# CodeWithJawad-eee_MPU6050__MPU6050.net
KiCad netlist of a schematic drawn in Altium Designer
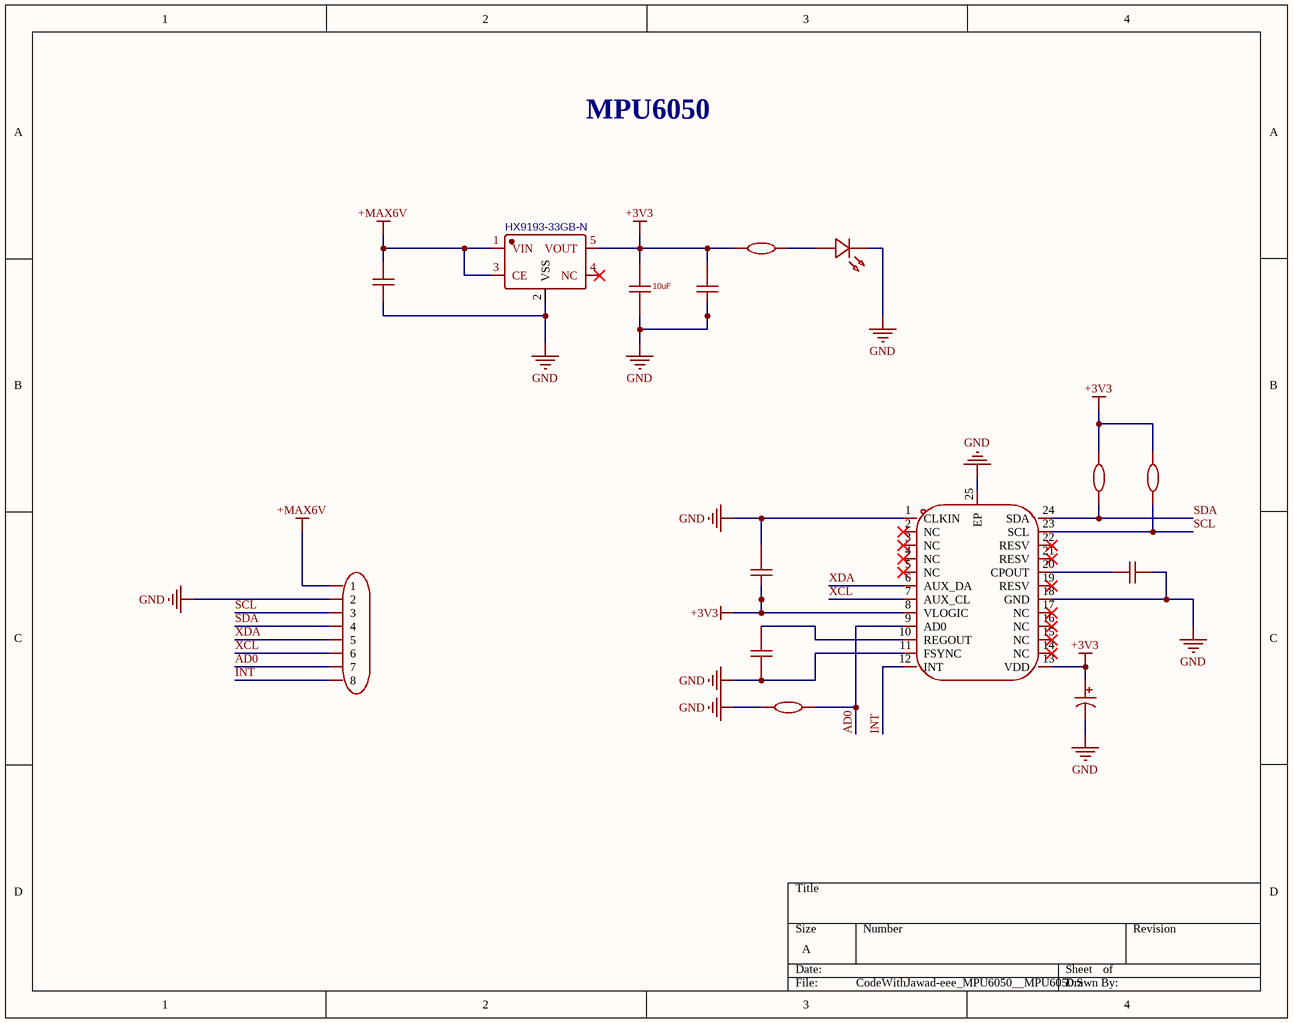
[diagram p0: CodeWithJawad-eee_MPU6050__MPU6050.SchDoc]

(export (version "E")
  (design (tool "Eeschema 10.0.6"))
  (components
    (comp (ref "C1")
      (value "100nF")
      (footprint "C0603")
      (fields
        (field (name "MANUFACTURER") "YAGEO(国巨)")
        (field (name "MANUFACTURER PART") "CC0603KRX7R9BB104")
        (field (name "TOLERANCE") "±10%")
      )
      (libsource (lib "SCH library") (part "CC0603KRX7R9BB104"))
    )
    (comp (ref "C2")
      (value "10uF")
      (footprint "C0603")
      (fields
        (field (name "MANUFACTURER") "SAMSUNG(三星)")
        (field (name "MANUFACTURER PART") "CL10A106KP8NNNC")
        (field (name "TOLERANCE") "±10%")
      )
      (libsource (lib "SCH library") (part "CL10A106KP8NNNC"))
    )
    (comp (ref "C3")
      (value "4.7uF")
      (footprint "C0603")
      (fields
        (field (name "MANUFACTURER") "SAMSUNG(三星)")
        (field (name "MANUFACTURER PART") "CL10A475KA8NQNC")
        (field (name "TOLERANCE") "±10%")
      )
      (libsource (lib "SCH library") (part "CL10A475KA8NQNC"))
    )
    (comp (ref "C4")
      (value "2.2nF")
      (footprint "C0603")
      (fields
        (field (name "MANUFACTURER") "YAGEO(国巨)")
        (field (name "MANUFACTURER PART") "CC0603KRX7R9BB222")
        (field (name "TOLERANCE") "±10%")
      )
      (libsource (lib "SCH library") (part "CC0603KRX7R9BB222"))
    )
    (comp (ref "C5")
      (value "100nF")
      (footprint "CAP-TH_BD5.0-P2.00-D0.8-FD")
      (fields
        (field (name "MANUFACTURER") "CX(承兴)")
        (field (name "MANUFACTURER PART") "KM104M050D11RR0VH2FP0")
        (field (name "TOLERANCE") "±20%")
      )
      (libsource (lib "SCH library") (part "KM104M050D11RR0VH2FP0"))
    )
    (comp (ref "C6")
      (value "100nF")
      (footprint "C0603")
      (fields
        (field (name "MANUFACTURER") "YAGEO(国巨)")
        (field (name "MANUFACTURER PART") "CC0603KRX7R9BB104")
        (field (name "TOLERANCE") "±10%")
      )
      (libsource (lib "SCH library") (part "CC0603KRX7R9BB104"))
    )
    (comp (ref "C7")
      (value "100nF")
      (footprint "C0603")
      (fields
        (field (name "MANUFACTURER") "YAGEO(国巨)")
        (field (name "MANUFACTURER PART") "CC0603KRX7R9BB104")
        (field (name "TOLERANCE") "±10%")
      )
      (libsource (lib "SCH library") (part "CC0603KRX7R9BB104"))
    )
    (comp (ref "LED1")
      (value "XL-1608SURC-06")
      (footprint "LED0603-RD_RED")
      (fields (field (name "MANUFACTURER") "XINGLIGHT(成兴光)"))
      (libsource (lib "SCH library") (part "XL-1608SURC-06"))
    )
    (comp (ref "P1")
      (value "2.54-1*8P母环保")
      (footprint "HDR-TH_8P-P2.54-V-F-1")
      (fields (field (name "MANUFACTURER") "BOOMELE(博穆精密)"))
      (libsource (lib "SCH library") (part "2.54-1*8P母环保"))
    )
    (comp (ref "R1")
      (value "2kΩ")
      (footprint "R0603")
      (fields
        (field (name "MANUFACTURER") "YAGEO(国巨)")
        (field (name "MANUFACTURER PART") "RC0603FR-072KL")
        (field (name "TOLERANCE") "±1%")
      )
      (libsource (lib "SCH library") (part "RC0603FR-072KL"))
    )
    (comp (ref "R2")
      (value "4.7kΩ")
      (footprint "R0603")
      (fields
        (field (name "MANUFACTURER") "YAGEO(国巨)")
        (field (name "MANUFACTURER PART") "RC0603FR-074K7L")
        (field (name "TOLERANCE") "±1%")
      )
      (libsource (lib "SCH library") (part "RC0603FR-074K7L"))
    )
    (comp (ref "R3")
      (value "4.7kΩ")
      (footprint "R0603")
      (fields
        (field (name "MANUFACTURER") "YAGEO(国巨)")
        (field (name "MANUFACTURER PART") "RC0603FR-074K7L")
        (field (name "TOLERANCE") "±1%")
      )
      (libsource (lib "SCH library") (part "RC0603FR-074K7L"))
    )
    (comp (ref "R4")
      (value "4.7kΩ")
      (footprint "R0603")
      (fields
        (field (name "MANUFACTURER") "YAGEO(国巨)")
        (field (name "MANUFACTURER PART") "RC0603FR-074K7L")
        (field (name "TOLERANCE") "±1%")
      )
      (libsource (lib "SCH library") (part "RC0603FR-074K7L"))
    )
    (comp (ref "U1")
      (value "HX9193-33GB-N")
      (footprint "SOT-23-5_L2.9-W1.6-P0.95-LS2.8-BL")
      (fields (field (name "MANUFACTURER") "HX(恒佳兴)") (field (name "CONTRIBUTOR") "lcsc"))
      (libsource (lib "SCH library") (part "HX9193-33GB-N"))
    )
    (comp (ref "U3")
      (value "MPU-6050")
      (footprint "QFN-24_L4.0-W4.0-P0.50-BL-EP2.7")
      (fields (field (name "MANUFACTURER") "TDK InvenSense(应美盛)"))
      (libsource (lib "SCH library") (part "MPU-6050"))
    )
  )
  (nets
    (net (code "1") (name "+3V3") (class "Default")
      (node (ref "C1") (pin "2") (pinfunction "2_2") (pintype "passive"))
      (node (ref "C2") (pin "2") (pinfunction "2_2") (pintype "passive"))
      (node (ref "C5") (pin "1") (pinfunction "1_1") (pintype "passive"))
      (node (ref "C6") (pin "1") (pinfunction "1_1") (pintype "passive"))
      (node (ref "R1") (pin "1") (pinfunction "1_1") (pintype "passive"))
      (node (ref "R2") (pin "2") (pinfunction "2_2") (pintype "passive"))
      (node (ref "R3") (pin "2") (pinfunction "2_2") (pintype "passive"))
      (node (ref "U1") (pin "5") (pinfunction "VOUT_5") (pintype "passive"))
      (node (ref "U3") (pin "13") (pinfunction "VDD_13") (pintype "passive"))
      (node (ref "U3") (pin "8") (pinfunction "VLOGIC_8") (pintype "passive"))
    )
    (net (code "2") (name "+MAX6V") (class "Default")
      (node (ref "C3") (pin "2") (pinfunction "2_2") (pintype "passive"))
      (node (ref "P1") (pin "1") (pinfunction "1_1") (pintype "passive"))
      (node (ref "U1") (pin "1") (pinfunction "VIN_1") (pintype "passive"))
      (node (ref "U1") (pin "3") (pinfunction "CE_3") (pintype "passive"))
    )
    (net (code "3") (name "/AD0") (class "Default")
      (node (ref "P1") (pin "7") (pinfunction "7_7") (pintype "passive"))
      (node (ref "R4") (pin "1") (pinfunction "1_1") (pintype "passive"))
      (node (ref "U3") (pin "9") (pinfunction "AD0_9") (pintype "passive"))
    )
    (net (code "4") (name "/INT") (class "Default")
      (node (ref "P1") (pin "8") (pinfunction "8_8") (pintype "passive"))
      (node (ref "U3") (pin "12") (pinfunction "INT_12") (pintype "passive"))
    )
    (net (code "5") (name "/SCL") (class "Default")
      (node (ref "P1") (pin "3") (pinfunction "3_3") (pintype "passive"))
      (node (ref "R3") (pin "1") (pinfunction "1_1") (pintype "passive"))
      (node (ref "U3") (pin "23") (pinfunction "SCL_23") (pintype "passive"))
    )
    (net (code "6") (name "/SDA") (class "Default")
      (node (ref "P1") (pin "4") (pinfunction "4_4") (pintype "passive"))
      (node (ref "R2") (pin "1") (pinfunction "1_1") (pintype "passive"))
      (node (ref "U3") (pin "24") (pinfunction "SDA_24") (pintype "passive"))
    )
    (net (code "7") (name "/XCL") (class "Default")
      (node (ref "P1") (pin "6") (pinfunction "6_6") (pintype "passive"))
      (node (ref "U3") (pin "7") (pinfunction "AUX_CL_7") (pintype "passive"))
    )
    (net (code "8") (name "/XDA") (class "Default")
      (node (ref "P1") (pin "5") (pinfunction "5_5") (pintype "passive"))
      (node (ref "U3") (pin "6") (pinfunction "AUX_DA_6") (pintype "passive"))
    )
    (net (code "9") (name "GND") (class "Default")
      (node (ref "C1") (pin "1") (pinfunction "1_1") (pintype "passive"))
      (node (ref "C2") (pin "1") (pinfunction "1_1") (pintype "passive"))
      (node (ref "C3") (pin "1") (pinfunction "1_1") (pintype "passive"))
      (node (ref "C4") (pin "2") (pinfunction "2_2") (pintype "passive"))
      (node (ref "C5") (pin "2") (pinfunction "2_2") (pintype "passive"))
      (node (ref "C6") (pin "2") (pinfunction "2_2") (pintype "passive"))
      (node (ref "C7") (pin "1") (pinfunction "1_1") (pintype "passive"))
      (node (ref "LED1") (pin "1") (pinfunction "K_1") (pintype "passive"))
      (node (ref "P1") (pin "2") (pinfunction "2_2") (pintype "passive"))
      (node (ref "R4") (pin "2") (pinfunction "2_2") (pintype "passive"))
      (node (ref "U1") (pin "2") (pinfunction "VSS_2") (pintype "passive"))
      (node (ref "U3") (pin "1") (pinfunction "CLKIN_1") (pintype "passive"))
      (node (ref "U3") (pin "11") (pinfunction "FSYNC_11") (pintype "passive"))
      (node (ref "U3") (pin "18") (pinfunction "GND_18") (pintype "passive"))
      (node (ref "U3") (pin "25") (pinfunction "EP_25") (pintype "passive"))
    )
    (net (code "10") (name "Net-(LED1-A)") (class "Default")
      (node (ref "LED1") (pin "2") (pinfunction "A_2") (pintype "passive"))
      (node (ref "R1") (pin "2") (pinfunction "2_2") (pintype "passive"))
    )
    (net (code "11") (name "Net-(U3-CPOUT)") (class "Default")
      (node (ref "C4") (pin "1") (pinfunction "1_1") (pintype "passive"))
      (node (ref "U3") (pin "20") (pinfunction "CPOUT_20") (pintype "passive"))
    )
    (net (code "12") (name "Net-(U3-REGOUT)") (class "Default")
      (node (ref "C7") (pin "2") (pinfunction "2_2") (pintype "passive"))
      (node (ref "U3") (pin "10") (pinfunction "REGOUT_10") (pintype "passive"))
    )
    (net (code "13") (name "unconnected-(U1-NC-Pad4)") (class "Default")
      (node (ref "U1") (pin "4") (pinfunction "NC_4") (pintype "passive+no_connect"))
    )
    (net (code "14") (name "unconnected-(U3-NC-Pad2)") (class "Default")
      (node (ref "U3") (pin "2") (pinfunction "NC_2") (pintype "passive+no_connect"))
    )
    (net (code "15") (name "unconnected-(U3-NC-Pad3)") (class "Default")
      (node (ref "U3") (pin "3") (pinfunction "NC_3") (pintype "passive+no_connect"))
    )
    (net (code "16") (name "unconnected-(U3-NC-Pad4)") (class "Default")
      (node (ref "U3") (pin "4") (pinfunction "NC_4") (pintype "passive+no_connect"))
    )
    (net (code "17") (name "unconnected-(U3-NC-Pad5)") (class "Default")
      (node (ref "U3") (pin "5") (pinfunction "NC_5") (pintype "passive+no_connect"))
    )
    (net (code "18") (name "unconnected-(U3-NC-Pad14)") (class "Default")
      (node (ref "U3") (pin "14") (pinfunction "NC_14") (pintype "passive+no_connect"))
    )
    (net (code "19") (name "unconnected-(U3-NC-Pad15)") (class "Default")
      (node (ref "U3") (pin "15") (pinfunction "NC_15") (pintype "passive+no_connect"))
    )
    (net (code "20") (name "unconnected-(U3-NC-Pad16)") (class "Default")
      (node (ref "U3") (pin "16") (pinfunction "NC_16") (pintype "passive+no_connect"))
    )
    (net (code "21") (name "unconnected-(U3-NC-Pad17)") (class "Default")
      (node (ref "U3") (pin "17") (pinfunction "NC_17") (pintype "passive+no_connect"))
    )
    (net (code "22") (name "unconnected-(U3-RESV-Pad19)") (class "Default")
      (node (ref "U3") (pin "19") (pinfunction "RESV_19") (pintype "passive+no_connect"))
    )
    (net (code "23") (name "unconnected-(U3-RESV-Pad21)") (class "Default")
      (node (ref "U3") (pin "21") (pinfunction "RESV_21") (pintype "passive+no_connect"))
    )
    (net (code "24") (name "unconnected-(U3-RESV-Pad22)") (class "Default")
      (node (ref "U3") (pin "22") (pinfunction "RESV_22") (pintype "passive+no_connect"))
    )
  )
)
